# buttons-DIP.net
KiCad netlist of a schematic drawn in EAGLE
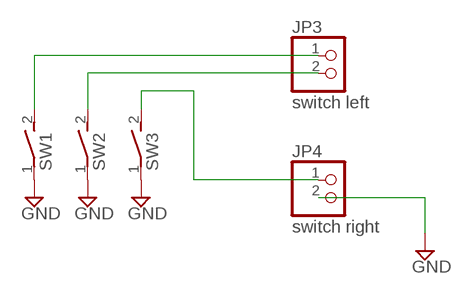
[diagram p0: schematic, sheet 1]

(export (version "E")
  (design (tool "Eeschema 10.0.6"))
  (components
    (comp (ref "JP3")
      (value "switch left")
      (footprint "eagle-import:1X02")
      (libsource (lib "eagle-import") (part "PINHD-1X2"))
    )
    (comp (ref "JP4")
      (value "switch right")
      (footprint "eagle-import:1X02")
      (libsource (lib "eagle-import") (part "PINHD-1X2"))
    )
    (comp (ref "SW1")
      (value "TVBP060.3INCH-PITCH")
      (footprint "eagle-import:TVBP06-0.3INCH")
      (libsource (lib "eagle-import") (part "TVBP060.3INCH-PITCH"))
    )
    (comp (ref "SW2")
      (value "TVBP060.3INCH-PITCH")
      (footprint "eagle-import:TVBP06-0.3INCH")
      (libsource (lib "eagle-import") (part "TVBP060.3INCH-PITCH"))
    )
    (comp (ref "SW3")
      (value "TVBP060.3INCH-PITCH")
      (footprint "eagle-import:TVBP06-0.3INCH")
      (libsource (lib "eagle-import") (part "TVBP060.3INCH-PITCH"))
    )
  )
  (nets
    (net (code "1") (name "GND") (class "Default")
      (node (ref "JP4") (pin "2") (pinfunction "2_2") (pintype "passive"))
      (node (ref "SW1") (pin "1") (pinfunction "1_1") (pintype "passive"))
      (node (ref "SW2") (pin "1") (pinfunction "1_1") (pintype "passive"))
      (node (ref "SW3") (pin "1") (pinfunction "1_1") (pintype "passive"))
    )
    (net (code "2") (name "Net-(JP3-Pad1)") (class "Default")
      (node (ref "JP3") (pin "1") (pinfunction "1_1") (pintype "passive"))
      (node (ref "SW1") (pin "2") (pinfunction "2_2") (pintype "passive"))
    )
    (net (code "3") (name "Net-(JP3-Pad2)") (class "Default")
      (node (ref "JP3") (pin "2") (pinfunction "2_2") (pintype "passive"))
      (node (ref "SW2") (pin "2") (pinfunction "2_2") (pintype "passive"))
    )
    (net (code "4") (name "Net-(JP4-Pad1)") (class "Default")
      (node (ref "JP4") (pin "1") (pinfunction "1_1") (pintype "passive"))
      (node (ref "SW3") (pin "2") (pinfunction "2_2") (pintype "passive"))
    )
  )
)
